# 1_WIZ750SR_W7500P.net
KiCad netlist of a schematic drawn in Altium Designer
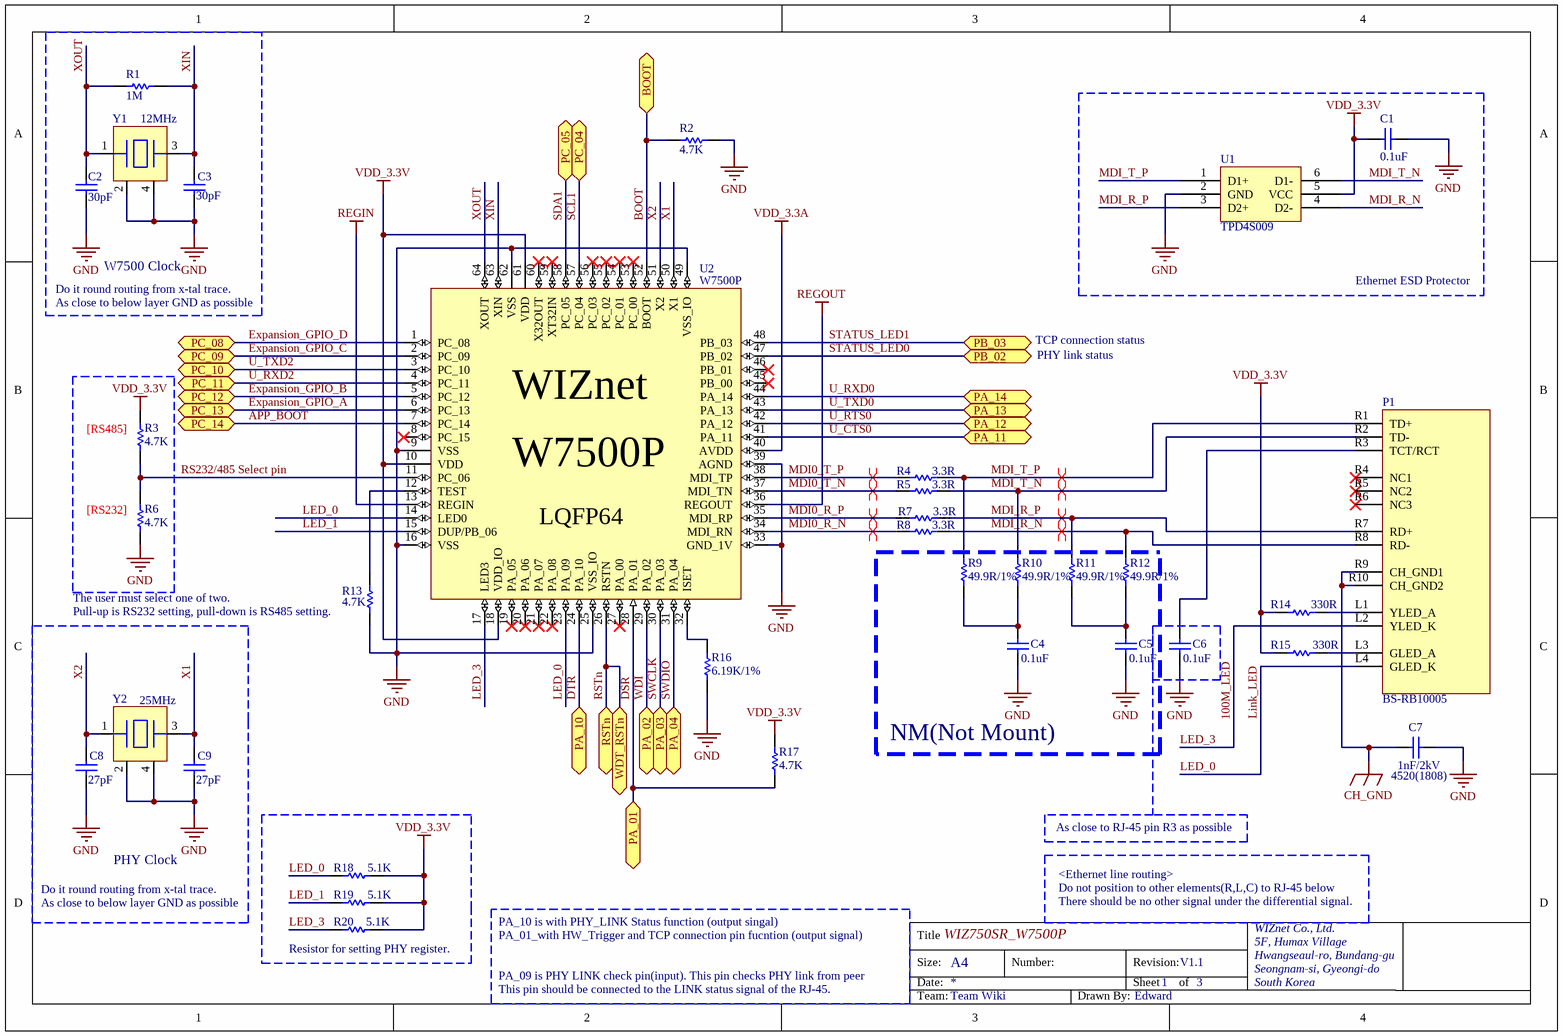
[diagram p0: 1.WIZ750SR_W7500P.SchDoc]

(export (version "E")
  (design (tool "Eeschema 10.0.6"))
  (components
    (comp (ref "C1")
      (value "0.1uF")
      (footprint "CAP-0402")
      (description "Ceramic CAP 0402(1005)")
      (libsource (lib "Scott_lib") (part "CAP-0402"))
    )
    (comp (ref "C2")
      (value "30pF")
      (footprint "CAP-0402")
      (description "Ceramic CAP 0402(1005)")
      (libsource (lib "Scott_lib") (part "CAP-0402"))
    )
    (comp (ref "C3")
      (value "30pF")
      (footprint "CAP-0402")
      (description "Ceramic CAP 0402(1005)")
      (libsource (lib "Scott_lib") (part "CAP-0402"))
    )
    (comp (ref "C4")
      (value "0.1uF")
      (footprint "CAP-0402")
      (description "Ceramic CAP 0402(1005)")
      (libsource (lib "Scott_lib") (part "CAP-0402"))
    )
    (comp (ref "C5")
      (value "0.1uF")
      (footprint "CAP-0402")
      (description "Ceramic CAP 0402(1005)")
      (libsource (lib "Scott_lib") (part "CAP-0402"))
    )
    (comp (ref "C6")
      (value "0.1uF")
      (footprint "CAP-0402")
      (description "Ceramic CAP 0402(1005)")
      (libsource (lib "Scott_lib") (part "CAP-0402"))
    )
    (comp (ref "C7")
      (value "1nF/2kV")
      (footprint "CAP-1808")
      (description "Ceramic CAP 1808(4520)")
      (libsource (lib "Scott_lib") (part "CAP-1808"))
    )
    (comp (ref "C8")
      (value "27pF")
      (footprint "CAP-0402")
      (description "Ceramic CAP 0402(1005)")
      (libsource (lib "Scott_lib") (part "CAP-0402"))
    )
    (comp (ref "C9")
      (value "27pF")
      (footprint "CAP-0402")
      (description "Ceramic CAP 0402(1005)")
      (libsource (lib "Scott_lib") (part "CAP-0402"))
    )
    (comp (ref "P1")
      (value "BS-RB10005")
      (footprint "RJ45-125BAG1A")
      (description "10/100 BASE-TX MAGJACK")
      (libsource (lib "Edward") (part "RB1-125BAG1A"))
    )
    (comp (ref "R1")
      (value "1M")
      (footprint "RES-0402")
      (description "RES-0402")
      (libsource (lib "Scott_lib") (part "RES-0402"))
    )
    (comp (ref "R2")
      (value "4.7K")
      (footprint "RES-0402")
      (description "RES-0402")
      (libsource (lib "Scott_lib") (part "RES-0402"))
    )
    (comp (ref "R3")
      (value "4.7K")
      (footprint "RES-0402")
      (description "RES-0402")
      (libsource (lib "Scott_lib") (part "RES-0402"))
    )
    (comp (ref "R4")
      (value "3.3R")
      (footprint "RES-0402")
      (description "RES-0402")
      (libsource (lib "Scott_lib") (part "RES-0402"))
    )
    (comp (ref "R5")
      (value "3.3R")
      (footprint "RES-0402")
      (description "RES-0402")
      (libsource (lib "Scott_lib") (part "RES-0402"))
    )
    (comp (ref "R6")
      (value "4.7K")
      (footprint "RES-0402")
      (description "RES-0402")
      (libsource (lib "Scott_lib") (part "RES-0402"))
    )
    (comp (ref "R7")
      (value "3.3R")
      (footprint "RES-0402")
      (description "RES-0402")
      (libsource (lib "Scott_lib") (part "RES-0402"))
    )
    (comp (ref "R8")
      (value "3.3R")
      (footprint "RES-0402")
      (description "RES-0402")
      (libsource (lib "Scott_lib") (part "RES-0402"))
    )
    (comp (ref "R9")
      (value "49.9R/1%")
      (footprint "RES-0402")
      (description "RES-0402")
      (libsource (lib "Scott_lib") (part "RES-0402"))
    )
    (comp (ref "R10")
      (value "49.9R/1%")
      (footprint "RES-0402")
      (description "RES-0402")
      (libsource (lib "Scott_lib") (part "RES-0402"))
    )
    (comp (ref "R11")
      (value "49.9R/1%")
      (footprint "RES-0402")
      (description "RES-0402")
      (libsource (lib "Scott_lib") (part "RES-0402"))
    )
    (comp (ref "R12")
      (value "49.9R/1%")
      (footprint "RES-0402")
      (description "RES-0402")
      (libsource (lib "Scott_lib") (part "RES-0402"))
    )
    (comp (ref "R13")
      (value "4.7K")
      (footprint "RES-0402")
      (description "RES-0402")
      (libsource (lib "Scott_lib") (part "RES-0402"))
    )
    (comp (ref "R14")
      (value "330R")
      (footprint "RES-0402")
      (description "RES-0402")
      (libsource (lib "Scott_lib") (part "RES-0402"))
    )
    (comp (ref "R15")
      (value "330R")
      (footprint "RES-0402")
      (description "RES-0402")
      (libsource (lib "Scott_lib") (part "RES-0402"))
    )
    (comp (ref "R16")
      (value "6.19K/1%")
      (footprint "RES-0402")
      (description "RES-0402")
      (libsource (lib "Scott_lib") (part "RES-0402"))
    )
    (comp (ref "R17")
      (value "4.7K")
      (footprint "RES-0402")
      (description "RES-0402")
      (libsource (lib "Scott_lib") (part "RES-0402"))
    )
    (comp (ref "R18")
      (value "5.1K")
      (footprint "RES-0402")
      (description "RES-0402")
      (libsource (lib "Scott_lib") (part "RES-0402"))
    )
    (comp (ref "R19")
      (value "5.1K")
      (footprint "RES-0402")
      (description "RES-0402")
      (libsource (lib "Scott_lib") (part "RES-0402"))
    )
    (comp (ref "R20")
      (value "5.1K")
      (footprint "RES-0402")
      (description "RES-0402")
      (libsource (lib "Scott_lib") (part "RES-0402"))
    )
    (comp (ref "U1")
      (value "TPD4S009")
      (footprint "SOT-23-6L")
      (description "6-PIN SOT DBVor DCK Package")
      (libsource (lib "tpd4s009_SOT") (part "tpd4s009"))
    )
    (comp (ref "U2")
      (value "W7500P")
      (footprint "W7500-LQFP64")
      (description "WIZnet ARM Cortex-M0, Add PHY")
      (libsource (lib "Scott_lib") (part "W7500P"))
    )
    (comp (ref "Y1")
      (value "12MHz")
      (footprint "OSC-TZ1067B")
      (description "X-tal 12MHz,3.2x2.5 SMD, CL=20pF")
      (libsource (lib "Scott_lib") (part "OSC-TZ1067B-12MHz"))
    )
    (comp (ref "Y2")
      (value "25MHz")
      (footprint "OSC-82J0626")
      (description "X-tal 25MHz,3.2x2.5 SMD, CL=18pF")
      (libsource (lib "Scott_lib") (part "OSC-82J0626-25MHz"))
    )
  )
  (nets
    (net (code "1") (name "/100M_LED") (class "Default")
      (node (ref "P1") (pin "L2") (pinfunction "YLED_K_L2") (pintype "passive"))
      (node (ref "R20") (pin "1") (pinfunction "1_1") (pintype "passive"))
      (node (ref "U2") (pin "17") (pinfunction "LED3_17") (pintype "bidirectional"))
    )
    (net (code "2") (name "/APP_BOOT") (class "Default")
      (node (ref "U2") (pin "7") (pinfunction "PC_14_7") (pintype "bidirectional"))
    )
    (net (code "3") (name "/BOOT") (class "Default")
      (node (ref "R2") (pin "2") (pinfunction "2_2") (pintype "passive"))
      (node (ref "U2") (pin "52") (pinfunction "BOOT_52") (pintype "bidirectional"))
    )
    (net (code "4") (name "/DSR") (class "Default")
      (node (ref "R17") (pin "2") (pinfunction "2_2") (pintype "passive"))
      (node (ref "U2") (pin "28") (pinfunction "PA_01_28") (pintype "input"))
    )
    (net (code "5") (name "/DTR") (class "Default")
      (node (ref "U2") (pin "24") (pinfunction "PA_10_24") (pintype "bidirectional"))
    )
    (net (code "6") (name "/Expansion_GPIO_A") (class "Default")
      (node (ref "U2") (pin "6") (pinfunction "PC_13_6") (pintype "bidirectional"))
    )
    (net (code "7") (name "/Expansion_GPIO_B") (class "Default")
      (node (ref "U2") (pin "5") (pinfunction "PC_12_5") (pintype "bidirectional"))
    )
    (net (code "8") (name "/Expansion_GPIO_C") (class "Default")
      (node (ref "U2") (pin "2") (pinfunction "PC_09_2") (pintype "bidirectional"))
    )
    (net (code "9") (name "/Expansion_GPIO_D") (class "Default")
      (node (ref "U2") (pin "1") (pinfunction "PC_08_1") (pintype "bidirectional"))
    )
    (net (code "10") (name "/LED_0") (class "Default")
      (node (ref "P1") (pin "L4") (pinfunction "GLED_K_L4") (pintype "passive"))
      (node (ref "R18") (pin "1") (pinfunction "1_1") (pintype "passive"))
      (node (ref "U2") (pin "14") (pinfunction "LED0_14") (pintype "bidirectional"))
      (node (ref "U2") (pin "23") (pinfunction "PA_09_23") (pintype "bidirectional"))
    )
    (net (code "11") (name "/LED_1") (class "Default")
      (node (ref "R19") (pin "1") (pinfunction "1_1") (pintype "passive"))
      (node (ref "U2") (pin "15") (pinfunction "DUP/PB_06_15") (pintype "bidirectional"))
    )
    (net (code "12") (name "/MDI0_R_N") (class "Default")
      (node (ref "R8") (pin "1") (pinfunction "1_1") (pintype "passive"))
      (node (ref "U2") (pin "34") (pinfunction "MDI_RN_34") (pintype "bidirectional"))
    )
    (net (code "13") (name "/MDI0_R_P") (class "Default")
      (node (ref "R7") (pin "1") (pinfunction "1_1") (pintype "passive"))
      (node (ref "U2") (pin "35") (pinfunction "MDI_RP_35") (pintype "bidirectional"))
    )
    (net (code "14") (name "/MDI0_T_N") (class "Default")
      (node (ref "R5") (pin "1") (pinfunction "1_1") (pintype "passive"))
      (node (ref "U2") (pin "37") (pinfunction "MDI_TN_37") (pintype "bidirectional"))
    )
    (net (code "15") (name "/MDI0_T_P") (class "Default")
      (node (ref "R4") (pin "1") (pinfunction "1_1") (pintype "passive"))
      (node (ref "U2") (pin "38") (pinfunction "MDI_TP_38") (pintype "bidirectional"))
    )
    (net (code "16") (name "/MDI_R_N") (class "Default")
      (node (ref "P1") (pin "R8") (pinfunction "RD-_R8") (pintype "passive"))
      (node (ref "R12") (pin "2") (pinfunction "2_2") (pintype "passive"))
      (node (ref "R8") (pin "2") (pinfunction "2_2") (pintype "passive"))
      (node (ref "U1") (pin "4") (pinfunction "D2-_4") (pintype "passive"))
    )
    (net (code "17") (name "/MDI_R_P") (class "Default")
      (node (ref "P1") (pin "R7") (pinfunction "RD+_R7") (pintype "passive"))
      (node (ref "R11") (pin "2") (pinfunction "2_2") (pintype "passive"))
      (node (ref "R7") (pin "2") (pinfunction "2_2") (pintype "passive"))
      (node (ref "U1") (pin "3") (pinfunction "D2+_3") (pintype "passive"))
    )
    (net (code "18") (name "/MDI_T_N") (class "Default")
      (node (ref "P1") (pin "R2") (pinfunction "TD-_R2") (pintype "passive"))
      (node (ref "R10") (pin "2") (pinfunction "2_2") (pintype "passive"))
      (node (ref "R5") (pin "2") (pinfunction "2_2") (pintype "passive"))
      (node (ref "U1") (pin "6") (pinfunction "D1-_6") (pintype "passive"))
    )
    (net (code "19") (name "/MDI_T_P") (class "Default")
      (node (ref "P1") (pin "R1") (pinfunction "TD+_R1") (pintype "passive"))
      (node (ref "R4") (pin "2") (pinfunction "2_2") (pintype "passive"))
      (node (ref "R9") (pin "2") (pinfunction "2_2") (pintype "passive"))
      (node (ref "U1") (pin "1") (pinfunction "D1+_1") (pintype "passive"))
    )
    (net (code "20") (name "/RS232{slash}485 Select pin") (class "Default")
      (node (ref "R3") (pin "1") (pinfunction "1_1") (pintype "passive"))
      (node (ref "R6") (pin "2") (pinfunction "2_2") (pintype "passive"))
      (node (ref "U2") (pin "11") (pinfunction "PC_06_11") (pintype "bidirectional"))
    )
    (net (code "21") (name "/RSTn") (class "Default")
      (node (ref "U2") (pin "26") (pinfunction "RSTN_26") (pintype "bidirectional"))
    )
    (net (code "22") (name "/SCL1") (class "Default")
      (node (ref "U2") (pin "57") (pinfunction "PC_04_57") (pintype "bidirectional"))
    )
    (net (code "23") (name "/SDA1") (class "Default")
      (node (ref "U2") (pin "58") (pinfunction "PC_05_58") (pintype "bidirectional"))
    )
    (net (code "24") (name "/STATUS_LED0") (class "Default")
      (node (ref "U2") (pin "47") (pinfunction "PB_02_47") (pintype "bidirectional"))
    )
    (net (code "25") (name "/STATUS_LED1") (class "Default")
      (node (ref "U2") (pin "48") (pinfunction "PB_03_48") (pintype "bidirectional"))
    )
    (net (code "26") (name "/SWCLK") (class "Default")
      (node (ref "U2") (pin "30") (pinfunction "PA_03_30") (pintype "bidirectional"))
    )
    (net (code "27") (name "/SWDIO") (class "Default")
      (node (ref "U2") (pin "31") (pinfunction "PA_04_31") (pintype "bidirectional"))
    )
    (net (code "28") (name "/U_CTS0") (class "Default")
      (node (ref "U2") (pin "41") (pinfunction "PA_11_41") (pintype "bidirectional"))
    )
    (net (code "29") (name "/U_RTS0") (class "Default")
      (node (ref "U2") (pin "42") (pinfunction "PA_12_42") (pintype "bidirectional"))
    )
    (net (code "30") (name "/U_RXD0") (class "Default")
      (node (ref "U2") (pin "44") (pinfunction "PA_14_44") (pintype "bidirectional"))
    )
    (net (code "31") (name "/U_RXD2") (class "Default")
      (node (ref "U2") (pin "4") (pinfunction "PC_11_4") (pintype "bidirectional"))
    )
    (net (code "32") (name "/U_TXD0") (class "Default")
      (node (ref "U2") (pin "43") (pinfunction "PA_13_43") (pintype "bidirectional"))
    )
    (net (code "33") (name "/U_TXD2") (class "Default")
      (node (ref "U2") (pin "3") (pinfunction "PC_10_3") (pintype "bidirectional"))
    )
    (net (code "34") (name "/WDI") (class "Default")
      (node (ref "U2") (pin "29") (pinfunction "PA_02_29") (pintype "bidirectional"))
    )
    (net (code "35") (name "/X1") (class "Default")
      (node (ref "C9") (pin "2") (pinfunction "2_2") (pintype "passive"))
      (node (ref "U2") (pin "50") (pinfunction "X1_50") (pintype "bidirectional"))
      (node (ref "Y2") (pin "3") (pinfunction "3_3") (pintype "passive"))
    )
    (net (code "36") (name "/X2") (class "Default")
      (node (ref "C8") (pin "2") (pinfunction "2_2") (pintype "passive"))
      (node (ref "U2") (pin "51") (pinfunction "X2_51") (pintype "bidirectional"))
      (node (ref "Y2") (pin "1") (pinfunction "1_1") (pintype "passive"))
    )
    (net (code "37") (name "/XIN") (class "Default")
      (node (ref "C3") (pin "2") (pinfunction "2_2") (pintype "passive"))
      (node (ref "R1") (pin "2") (pinfunction "2_2") (pintype "passive"))
      (node (ref "U2") (pin "63") (pinfunction "XIN_63") (pintype "bidirectional"))
      (node (ref "Y1") (pin "3") (pinfunction "3_3") (pintype "passive"))
    )
    (net (code "38") (name "/XOUT") (class "Default")
      (node (ref "C2") (pin "2") (pinfunction "2_2") (pintype "passive"))
      (node (ref "R1") (pin "1") (pinfunction "1_1") (pintype "passive"))
      (node (ref "U2") (pin "64") (pinfunction "XOUT_64") (pintype "bidirectional"))
      (node (ref "Y1") (pin "1") (pinfunction "1_1") (pintype "passive"))
    )
    (net (code "39") (name "CH_GND") (class "Default")
      (node (ref "C7") (pin "2") (pinfunction "2_2") (pintype "passive"))
      (node (ref "P1") (pin "R10") (pinfunction "CH_GND2_R10") (pintype "passive"))
      (node (ref "P1") (pin "R9") (pinfunction "CH_GND1_R9") (pintype "passive"))
    )
    (net (code "40") (name "GND") (class "Default")
      (node (ref "C1") (pin "1") (pinfunction "1_1") (pintype "passive"))
      (node (ref "C2") (pin "1") (pinfunction "1_1") (pintype "passive"))
      (node (ref "C3") (pin "1") (pinfunction "1_1") (pintype "passive"))
      (node (ref "C4") (pin "1") (pinfunction "1_1") (pintype "passive"))
      (node (ref "C5") (pin "1") (pinfunction "1_1") (pintype "passive"))
      (node (ref "C6") (pin "1") (pinfunction "1_1") (pintype "passive"))
      (node (ref "C7") (pin "1") (pinfunction "1_1") (pintype "passive"))
      (node (ref "C8") (pin "1") (pinfunction "1_1") (pintype "passive"))
      (node (ref "C9") (pin "1") (pinfunction "1_1") (pintype "passive"))
      (node (ref "R13") (pin "1") (pinfunction "1_1") (pintype "passive"))
      (node (ref "R16") (pin "1") (pinfunction "1_1") (pintype "passive"))
      (node (ref "R2") (pin "1") (pinfunction "1_1") (pintype "passive"))
      (node (ref "R6") (pin "1") (pinfunction "1_1") (pintype "passive"))
      (node (ref "U1") (pin "2") (pinfunction "GND_2") (pintype "passive"))
      (node (ref "U2") (pin "16") (pinfunction "VSS_16") (pintype "bidirectional"))
      (node (ref "U2") (pin "25") (pinfunction "VSS_IO_25") (pintype "bidirectional"))
      (node (ref "U2") (pin "33") (pinfunction "GND_1V_33") (pintype "bidirectional"))
      (node (ref "U2") (pin "39") (pinfunction "AGND_39") (pintype "bidirectional"))
      (node (ref "U2") (pin "49") (pinfunction "VSS_IO_49") (pintype "bidirectional"))
      (node (ref "U2") (pin "62") (pinfunction "VSS_62") (pintype "power_in"))
      (node (ref "U2") (pin "9") (pinfunction "VSS_9") (pintype "power_in"))
      (node (ref "Y1") (pin "2") (pinfunction "2_2") (pintype "passive"))
      (node (ref "Y1") (pin "4") (pinfunction "4_4") (pintype "passive"))
      (node (ref "Y2") (pin "2") (pinfunction "2_2") (pintype "passive"))
      (node (ref "Y2") (pin "4") (pinfunction "4_4") (pintype "passive"))
    )
    (net (code "41") (name "Net-(C4-Pad2)") (class "Default")
      (node (ref "C4") (pin "2") (pinfunction "2_2") (pintype "passive"))
      (node (ref "R10") (pin "1") (pinfunction "1_1") (pintype "passive"))
      (node (ref "R9") (pin "1") (pinfunction "1_1") (pintype "passive"))
    )
    (net (code "42") (name "Net-(C5-Pad2)") (class "Default")
      (node (ref "C5") (pin "2") (pinfunction "2_2") (pintype "passive"))
      (node (ref "R11") (pin "1") (pinfunction "1_1") (pintype "passive"))
      (node (ref "R12") (pin "1") (pinfunction "1_1") (pintype "passive"))
    )
    (net (code "43") (name "Net-(P1-GLED_A)") (class "Default")
      (node (ref "P1") (pin "L3") (pinfunction "GLED_A_L3") (pintype "passive"))
      (node (ref "R15") (pin "2") (pinfunction "2_2") (pintype "passive"))
    )
    (net (code "44") (name "Net-(P1-TCT{slash}RCT)") (class "Default")
      (node (ref "C6") (pin "2") (pinfunction "2_2") (pintype "passive"))
      (node (ref "P1") (pin "R3") (pinfunction "TCT/RCT_R3") (pintype "passive"))
    )
    (net (code "45") (name "Net-(P1-YLED_A)") (class "Default")
      (node (ref "P1") (pin "L1") (pinfunction "YLED_A_L1") (pintype "passive"))
      (node (ref "R14") (pin "2") (pinfunction "2_2") (pintype "passive"))
    )
    (net (code "46") (name "Net-(U2-ISET)") (class "Default")
      (node (ref "R16") (pin "2") (pinfunction "2_2") (pintype "passive"))
      (node (ref "U2") (pin "32") (pinfunction "ISET_32") (pintype "bidirectional"))
    )
    (net (code "47") (name "Net-(U2-TEST)") (class "Default")
      (node (ref "R13") (pin "2") (pinfunction "2_2") (pintype "passive"))
      (node (ref "U2") (pin "12") (pinfunction "TEST_12") (pintype "bidirectional"))
    )
    (net (code "48") (name "REGIN") (class "Default")
      (node (ref "U2") (pin "13") (pinfunction "REGIN_13") (pintype "bidirectional"))
    )
    (net (code "49") (name "REGOUT") (class "Default")
      (node (ref "U2") (pin "36") (pinfunction "REGOUT_36") (pintype "bidirectional"))
    )
    (net (code "50") (name "VDD_3.3A") (class "Default")
      (node (ref "U2") (pin "40") (pinfunction "AVDD_40") (pintype "bidirectional"))
    )
    (net (code "51") (name "VDD_3.3V") (class "Default")
      (node (ref "C1") (pin "2") (pinfunction "2_2") (pintype "passive"))
      (node (ref "R14") (pin "1") (pinfunction "1_1") (pintype "passive"))
      (node (ref "R15") (pin "1") (pinfunction "1_1") (pintype "passive"))
      (node (ref "R17") (pin "1") (pinfunction "1_1") (pintype "passive"))
      (node (ref "R18") (pin "2") (pinfunction "2_2") (pintype "passive"))
      (node (ref "R19") (pin "2") (pinfunction "2_2") (pintype "passive"))
      (node (ref "R20") (pin "2") (pinfunction "2_2") (pintype "passive"))
      (node (ref "R3") (pin "2") (pinfunction "2_2") (pintype "passive"))
      (node (ref "U1") (pin "5") (pinfunction "VCC_5") (pintype "passive"))
      (node (ref "U2") (pin "10") (pinfunction "VDD_10") (pintype "power_in"))
      (node (ref "U2") (pin "18") (pinfunction "VDD_IO_18") (pintype "bidirectional"))
      (node (ref "U2") (pin "61") (pinfunction "VDD_61") (pintype "power_in"))
    )
    (net (code "52") (name "unconnected-(P1-NC1-PadR4)") (class "Default")
      (node (ref "P1") (pin "R4") (pinfunction "NC1_R4") (pintype "passive+no_connect"))
    )
    (net (code "53") (name "unconnected-(P1-NC2-PadR5)") (class "Default")
      (node (ref "P1") (pin "R5") (pinfunction "NC2_R5") (pintype "passive+no_connect"))
    )
    (net (code "54") (name "unconnected-(P1-NC3-PadR6)") (class "Default")
      (node (ref "P1") (pin "R6") (pinfunction "NC3_R6") (pintype "passive+no_connect"))
    )
    (net (code "55") (name "unconnected-(U2-PA_00-Pad27)") (class "Default")
      (node (ref "U2") (pin "27") (pinfunction "PA_00_27") (pintype "bidirectional+no_connect"))
    )
    (net (code "56") (name "unconnected-(U2-PA_05-Pad19)") (class "Default")
      (node (ref "U2") (pin "19") (pinfunction "PA_05_19") (pintype "bidirectional+no_connect"))
    )
    (net (code "57") (name "unconnected-(U2-PA_06-Pad20)") (class "Default")
      (node (ref "U2") (pin "20") (pinfunction "PA_06_20") (pintype "bidirectional+no_connect"))
    )
    (net (code "58") (name "unconnected-(U2-PA_07-Pad21)") (class "Default")
      (node (ref "U2") (pin "21") (pinfunction "PA_07_21") (pintype "bidirectional+no_connect"))
    )
    (net (code "59") (name "unconnected-(U2-PA_08-Pad22)") (class "Default")
      (node (ref "U2") (pin "22") (pinfunction "PA_08_22") (pintype "bidirectional+no_connect"))
    )
    (net (code "60") (name "unconnected-(U2-PB_00-Pad45)") (class "Default")
      (node (ref "U2") (pin "45") (pinfunction "PB_00_45") (pintype "bidirectional+no_connect"))
    )
    (net (code "61") (name "unconnected-(U2-PB_01-Pad46)") (class "Default")
      (node (ref "U2") (pin "46") (pinfunction "PB_01_46") (pintype "bidirectional+no_connect"))
    )
    (net (code "62") (name "unconnected-(U2-PC_00-Pad53)") (class "Default")
      (node (ref "U2") (pin "53") (pinfunction "PC_00_53") (pintype "bidirectional+no_connect"))
    )
    (net (code "63") (name "unconnected-(U2-PC_01-Pad54)") (class "Default")
      (node (ref "U2") (pin "54") (pinfunction "PC_01_54") (pintype "bidirectional+no_connect"))
    )
    (net (code "64") (name "unconnected-(U2-PC_02-Pad55)") (class "Default")
      (node (ref "U2") (pin "55") (pinfunction "PC_02_55") (pintype "bidirectional+no_connect"))
    )
    (net (code "65") (name "unconnected-(U2-PC_03-Pad56)") (class "Default")
      (node (ref "U2") (pin "56") (pinfunction "PC_03_56") (pintype "bidirectional+no_connect"))
    )
    (net (code "66") (name "unconnected-(U2-PC_15-Pad8)") (class "Default")
      (node (ref "U2") (pin "8") (pinfunction "PC_15_8") (pintype "bidirectional+no_connect"))
    )
    (net (code "67") (name "unconnected-(U2-X32OUT-Pad60)") (class "Default")
      (node (ref "U2") (pin "60") (pinfunction "X32OUT_60") (pintype "bidirectional+no_connect"))
    )
    (net (code "68") (name "unconnected-(U2-XT32IN-Pad59)") (class "Default")
      (node (ref "U2") (pin "59") (pinfunction "XT32IN_59") (pintype "bidirectional+no_connect"))
    )
  )
)
